# MotorControllerV2.net
KiCad netlist of a schematic drawn in EAGLE
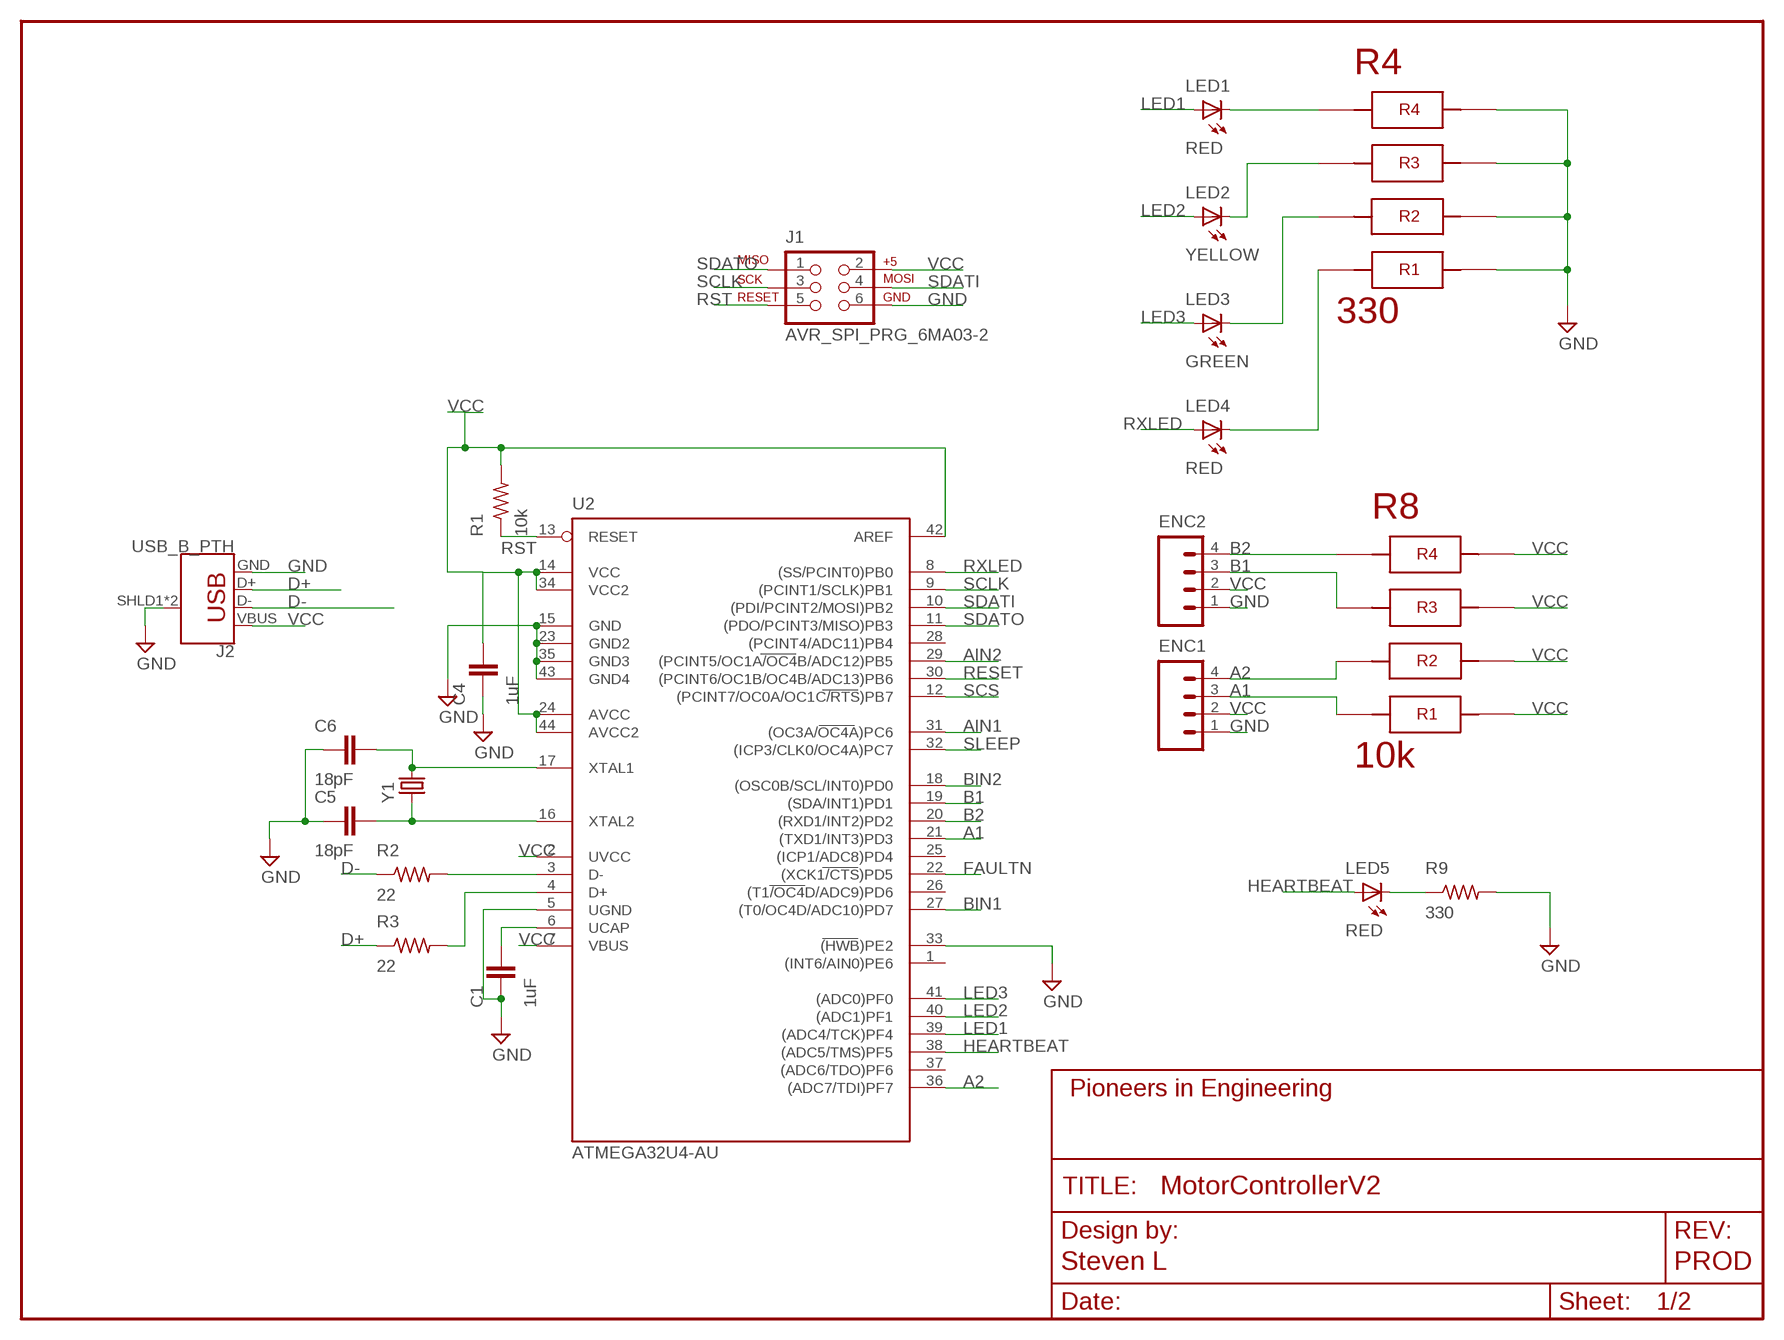
[diagram p0: schematic, sheet 1]
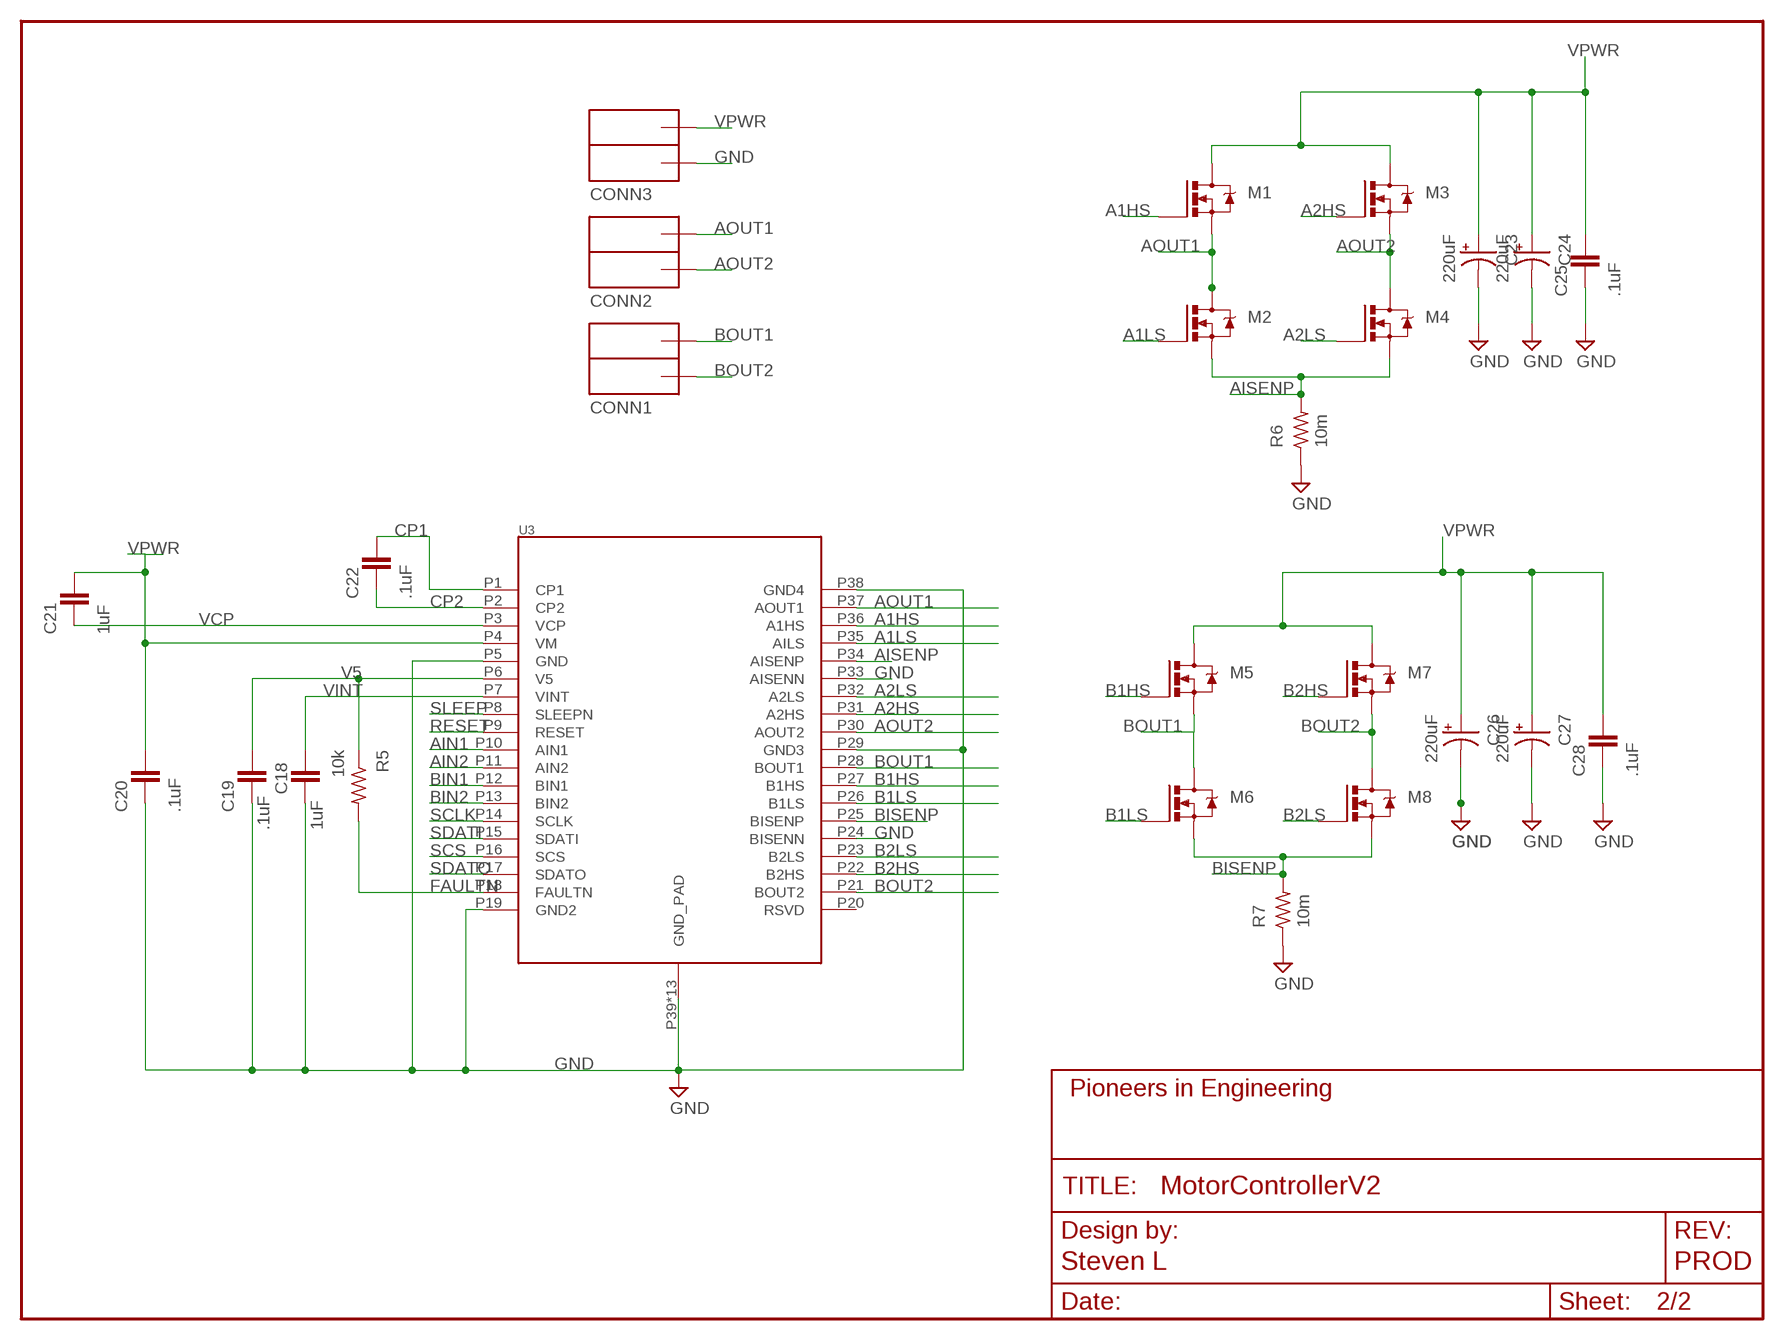
[diagram p1: schematic, sheet 2]

(export (version "E")
  (design (tool "Eeschema 10.0.6"))
  (components
    (comp (ref "C18")
      (value "1uF")
      (footprint "eagle-import:0603-CAP")
      (libsource (lib "eagle-import") (part "CAP0603-CAP"))
    )
    (comp (ref "C19")
      (value ".1uF")
      (footprint "eagle-import:0603-CAP")
      (libsource (lib "eagle-import") (part "CAP0603-CAP"))
    )
    (comp (ref "C20")
      (value ".1uF")
      (footprint "eagle-import:0603-CAP")
      (libsource (lib "eagle-import") (part "CAP0603-CAP"))
    )
    (comp (ref "C21")
      (value "1uF")
      (footprint "eagle-import:0603-CAP")
      (libsource (lib "eagle-import") (part "CAP0603-CAP"))
    )
    (comp (ref "C22")
      (value ".1uF")
      (footprint "eagle-import:0603-CAP")
      (libsource (lib "eagle-import") (part "CAP0603-CAP"))
    )
    (comp (ref "C23")
      (value "220uF")
      (footprint "eagle-import:NIPPON_F80")
      (libsource (lib "eagle-import") (part "CAP_POLF80"))
    )
    (comp (ref "C24")
      (value "220uF")
      (footprint "eagle-import:NIPPON_F80")
      (libsource (lib "eagle-import") (part "CAP_POLF80"))
    )
    (comp (ref "C25")
      (value ".1uF")
      (footprint "eagle-import:0603-CAP")
      (libsource (lib "eagle-import") (part "CAP0603-CAP"))
    )
    (comp (ref "C26")
      (value "220uF")
      (footprint "eagle-import:NIPPON_F80")
      (libsource (lib "eagle-import") (part "CAP_POLF80"))
    )
    (comp (ref "C27")
      (value "220uF")
      (footprint "eagle-import:NIPPON_F80")
      (libsource (lib "eagle-import") (part "CAP_POLF80"))
    )
    (comp (ref "C28")
      (value ".1uF")
      (footprint "eagle-import:0603-CAP")
      (libsource (lib "eagle-import") (part "CAP0603-CAP"))
    )
    (comp (ref "CONN1")
      (value "ANDERSONVERTICAL")
      (footprint "eagle-import:ANDERSON_VERTICAL")
      (libsource (lib "eagle-import") (part "ANDERSONVERTICAL"))
    )
    (comp (ref "CONN2")
      (value "ANDERSONVERTICAL")
      (footprint "eagle-import:ANDERSON_VERTICAL")
      (libsource (lib "eagle-import") (part "ANDERSONVERTICAL"))
    )
    (comp (ref "CONN3")
      (value "ANDERSONVERTICAL")
      (footprint "eagle-import:ANDERSON_VERTICAL")
      (libsource (lib "eagle-import") (part "ANDERSONVERTICAL"))
    )
    (comp (ref "M1")
      (value "NMOS_CSD17579Q3A")
      (footprint "eagle-import:DNH0008A")
      (fields (field (name "PART_NO") "CSD17579Q3A"))
      (libsource (lib "eagle-import") (part "NMOS_CSD17579Q3A"))
    )
    (comp (ref "M2")
      (value "NMOS_CSD17579Q3A")
      (footprint "eagle-import:DNH0008A")
      (fields (field (name "PART_NO") "CSD17579Q3A"))
      (libsource (lib "eagle-import") (part "NMOS_CSD17579Q3A"))
    )
    (comp (ref "M3")
      (value "NMOS_CSD17579Q3A")
      (footprint "eagle-import:DNH0008A")
      (fields (field (name "PART_NO") "CSD17579Q3A"))
      (libsource (lib "eagle-import") (part "NMOS_CSD17579Q3A"))
    )
    (comp (ref "M4")
      (value "NMOS_CSD17579Q3A")
      (footprint "eagle-import:DNH0008A")
      (fields (field (name "PART_NO") "CSD17579Q3A"))
      (libsource (lib "eagle-import") (part "NMOS_CSD17579Q3A"))
    )
    (comp (ref "M5")
      (value "NMOS_CSD17579Q3A")
      (footprint "eagle-import:DNH0008A")
      (fields (field (name "PART_NO") "CSD17579Q3A"))
      (libsource (lib "eagle-import") (part "NMOS_CSD17579Q3A"))
    )
    (comp (ref "M6")
      (value "NMOS_CSD17579Q3A")
      (footprint "eagle-import:DNH0008A")
      (fields (field (name "PART_NO") "CSD17579Q3A"))
      (libsource (lib "eagle-import") (part "NMOS_CSD17579Q3A"))
    )
    (comp (ref "M7")
      (value "NMOS_CSD17579Q3A")
      (footprint "eagle-import:DNH0008A")
      (fields (field (name "PART_NO") "CSD17579Q3A"))
      (libsource (lib "eagle-import") (part "NMOS_CSD17579Q3A"))
    )
    (comp (ref "M8")
      (value "NMOS_CSD17579Q3A")
      (footprint "eagle-import:DNH0008A")
      (fields (field (name "PART_NO") "CSD17579Q3A"))
      (libsource (lib "eagle-import") (part "NMOS_CSD17579Q3A"))
    )
    (comp (ref "R5")
      (value "10k")
      (footprint "eagle-import:R0603")
      (fields (field (name "MANUFACTURER") "Rohm Semiconductor"))
      (libsource (lib "eagle-import") (part "R-US_R0603"))
    )
    (comp (ref "R6")
      (value "10m")
      (footprint "eagle-import:R2512")
      (libsource (lib "eagle-import") (part "R-US_R2512"))
    )
    (comp (ref "R7")
      (value "10m")
      (footprint "eagle-import:R2512")
      (libsource (lib "eagle-import") (part "R-US_R2512"))
    )
    (comp (ref "U3")
      (value "DRV8704")
      (footprint "eagle-import:HTSSOP(38)")
      (libsource (lib "eagle-import") (part "DRV8704"))
    )
    (comp (ref "C1")
      (value "1uF")
      (footprint "eagle-import:0603-CAP")
      (libsource (lib "eagle-import") (part "CAP0603-CAP"))
    )
    (comp (ref "C4")
      (value "1uF")
      (footprint "eagle-import:0603-CAP")
      (libsource (lib "eagle-import") (part "CAP0603-CAP"))
    )
    (comp (ref "C5")
      (value "18pF")
      (footprint "eagle-import:0603-CAP")
      (libsource (lib "eagle-import") (part "CAP0603-CAP"))
    )
    (comp (ref "C6")
      (value "18pF")
      (footprint "eagle-import:0603-CAP")
      (libsource (lib "eagle-import") (part "CAP0603-CAP"))
    )
    (comp (ref "ENC1")
      (value "M041X04-MTA")
      (footprint "eagle-import:1X04-MTA")
      (libsource (lib "eagle-import") (part "M041X04-MTA"))
    )
    (comp (ref "ENC2")
      (value "M041X04-MTA")
      (footprint "eagle-import:1X04-MTA")
      (libsource (lib "eagle-import") (part "M041X04-MTA"))
    )
    (comp (ref "J1")
      (value "AVR_SPI_PRG_6MA03-2")
      (footprint "eagle-import:MA03-2")
      (libsource (lib "eagle-import") (part "AVR_SPI_PRG_6MA03-2"))
    )
    (comp (ref "J2")
      (value "USB_B_PTH")
      (footprint "eagle-import:USB-B-PTH")
      (libsource (lib "eagle-import") (part "USB_B_PTH"))
    )
    (comp (ref "LED1")
      (value "RED")
      (footprint "eagle-import:LED-1206")
      (libsource (lib "eagle-import") (part "LED1206"))
    )
    (comp (ref "LED2")
      (value "YELLOW")
      (footprint "eagle-import:LED-1206")
      (libsource (lib "eagle-import") (part "LED1206"))
    )
    (comp (ref "LED3")
      (value "GREEN")
      (footprint "eagle-import:LED-1206")
      (libsource (lib "eagle-import") (part "LED1206"))
    )
    (comp (ref "LED4")
      (value "RED")
      (footprint "eagle-import:LED-1206")
      (libsource (lib "eagle-import") (part "LED1206"))
    )
    (comp (ref "LED5")
      (value "RED")
      (footprint "eagle-import:LED-1206")
      (libsource (lib "eagle-import") (part "LED1206"))
    )
    (comp (ref "R1")
      (value "10k")
      (footprint "eagle-import:R0603")
      (fields (field (name "MANUFACTURER") "Rohm Semiconductor"))
      (libsource (lib "eagle-import") (part "R-US_R0603"))
    )
    (comp (ref "R2")
      (value "22")
      (footprint "eagle-import:R0603")
      (fields (field (name "MANUFACTURER") "Rohm Semiconductor"))
      (libsource (lib "eagle-import") (part "R-US_R0603"))
    )
    (comp (ref "R3")
      (value "22")
      (footprint "eagle-import:R0603")
      (fields (field (name "MANUFACTURER") "Rohm Semiconductor"))
      (libsource (lib "eagle-import") (part "R-US_R0603"))
    )
    (comp (ref "R4")
      (value "330")
      (footprint "eagle-import:4X-0603")
      (libsource (lib "eagle-import") (part "4X-0603"))
    )
    (comp (ref "R8")
      (value "10k")
      (footprint "eagle-import:4X-0603")
      (libsource (lib "eagle-import") (part "4X-0603"))
    )
    (comp (ref "R9")
      (value "330")
      (footprint "eagle-import:R0603")
      (fields (field (name "MANUFACTURER") "Rohm Semiconductor"))
      (libsource (lib "eagle-import") (part "R-US_R0603"))
    )
    (comp (ref "U2")
      (value "ATMEGA32U4-AU")
      (footprint "eagle-import:TQFP44")
      (libsource (lib "eagle-import") (part "ATMEGA32U4-AU"))
    )
    (comp (ref "Y1")
      (value "CRYSTAL10.5X4.8")
      (footprint "eagle-import:CRYSTAL-SMD-10.5X4.8-2PIN")
      (libsource (lib "eagle-import") (part "CRYSTAL10.5X4.8"))
    )
  )
  (nets
    (net (code "1") (name "A1") (class "Default")
      (node (ref "ENC1") (pin "3") (pinfunction "3_3") (pintype "passive"))
      (node (ref "R8") (pin "8") (pinfunction "8_8") (pintype "bidirectional"))
      (node (ref "U2") (pin "21") (pinfunction "(TXD1/INT3)PD3_21") (pintype "bidirectional"))
    )
    (net (code "2") (name "A1HS") (class "Default")
      (node (ref "M1") (pin "4") (pinfunction "G_4") (pintype "passive"))
      (node (ref "U3") (pin "P36") (pinfunction "A1HS_P36") (pintype "bidirectional"))
    )
    (net (code "3") (name "A1LS") (class "Default")
      (node (ref "M2") (pin "4") (pinfunction "G_4") (pintype "passive"))
      (node (ref "U3") (pin "P35") (pinfunction "AILS_P35") (pintype "bidirectional"))
    )
    (net (code "4") (name "A2") (class "Default")
      (node (ref "ENC1") (pin "4") (pinfunction "4_4") (pintype "passive"))
      (node (ref "R8") (pin "7") (pinfunction "7_7") (pintype "bidirectional"))
      (node (ref "U2") (pin "36") (pinfunction "(ADC7/TDI)PF7_36") (pintype "bidirectional"))
    )
    (net (code "5") (name "A2HS") (class "Default")
      (node (ref "M3") (pin "4") (pinfunction "G_4") (pintype "passive"))
      (node (ref "U3") (pin "P31") (pinfunction "A2HS_P31") (pintype "bidirectional"))
    )
    (net (code "6") (name "A2LS") (class "Default")
      (node (ref "M4") (pin "4") (pinfunction "G_4") (pintype "passive"))
      (node (ref "U3") (pin "P32") (pinfunction "A2LS_P32") (pintype "bidirectional"))
    )
    (net (code "7") (name "AIN1") (class "Default")
      (node (ref "U2") (pin "31") (pinfunction "(OC3A/OC4A)PC6_31") (pintype "bidirectional"))
      (node (ref "U3") (pin "P10") (pinfunction "AIN1_P10") (pintype "bidirectional"))
    )
    (net (code "8") (name "AIN2") (class "Default")
      (node (ref "U2") (pin "29") (pinfunction "(PCINT5/OC1A/OC4B/ADC12)PB5_29") (pintype "bidirectional"))
      (node (ref "U3") (pin "P11") (pinfunction "AIN2_P11") (pintype "bidirectional"))
    )
    (net (code "9") (name "AISENP") (class "Default")
      (node (ref "M2") (pin "1") (pinfunction "S_1") (pintype "passive"))
      (node (ref "M2") (pin "2") (pinfunction "S_2") (pintype "passive"))
      (node (ref "M2") (pin "3") (pinfunction "S_3") (pintype "passive"))
      (node (ref "M4") (pin "1") (pinfunction "S_1") (pintype "passive"))
      (node (ref "M4") (pin "2") (pinfunction "S_2") (pintype "passive"))
      (node (ref "M4") (pin "3") (pinfunction "S_3") (pintype "passive"))
      (node (ref "R6") (pin "2") (pinfunction "2_2") (pintype "passive"))
      (node (ref "U3") (pin "P34") (pinfunction "AISENP_P34") (pintype "bidirectional"))
    )
    (net (code "10") (name "AOUT1") (class "Default")
      (node (ref "CONN2") (pin "PIN1") (pinfunction "OUTB_PIN1") (pintype "bidirectional"))
      (node (ref "M1") (pin "1") (pinfunction "S_1") (pintype "passive"))
      (node (ref "M1") (pin "2") (pinfunction "S_2") (pintype "passive"))
      (node (ref "M1") (pin "3") (pinfunction "S_3") (pintype "passive"))
      (node (ref "M2") (pin "5") (pinfunction "D_5") (pintype "passive"))
      (node (ref "M2") (pin "6") (pinfunction "D_6") (pintype "passive"))
      (node (ref "M2") (pin "7") (pinfunction "D_7") (pintype "passive"))
      (node (ref "M2") (pin "8") (pinfunction "D_8") (pintype "passive"))
      (node (ref "M2") (pin "9") (pinfunction "D_9") (pintype "passive"))
      (node (ref "U3") (pin "P37") (pinfunction "AOUT1_P37") (pintype "bidirectional"))
    )
    (net (code "11") (name "AOUT2") (class "Default")
      (node (ref "CONN2") (pin "PIN2") (pinfunction "OUTA_PIN2") (pintype "bidirectional"))
      (node (ref "M3") (pin "1") (pinfunction "S_1") (pintype "passive"))
      (node (ref "M3") (pin "2") (pinfunction "S_2") (pintype "passive"))
      (node (ref "M3") (pin "3") (pinfunction "S_3") (pintype "passive"))
      (node (ref "M4") (pin "5") (pinfunction "D_5") (pintype "passive"))
      (node (ref "M4") (pin "6") (pinfunction "D_6") (pintype "passive"))
      (node (ref "M4") (pin "7") (pinfunction "D_7") (pintype "passive"))
      (node (ref "M4") (pin "8") (pinfunction "D_8") (pintype "passive"))
      (node (ref "M4") (pin "9") (pinfunction "D_9") (pintype "passive"))
      (node (ref "U3") (pin "P30") (pinfunction "AOUT2_P30") (pintype "bidirectional"))
    )
    (net (code "12") (name "B1") (class "Default")
      (node (ref "ENC2") (pin "3") (pinfunction "3_3") (pintype "passive"))
      (node (ref "R8") (pin "6") (pinfunction "6_6") (pintype "bidirectional"))
      (node (ref "U2") (pin "19") (pinfunction "(SDA/INT1)PD1_19") (pintype "bidirectional"))
    )
    (net (code "13") (name "B1HS") (class "Default")
      (node (ref "M5") (pin "4") (pinfunction "G_4") (pintype "passive"))
      (node (ref "U3") (pin "P27") (pinfunction "B1HS_P27") (pintype "bidirectional"))
    )
    (net (code "14") (name "B1LS") (class "Default")
      (node (ref "M6") (pin "4") (pinfunction "G_4") (pintype "passive"))
      (node (ref "U3") (pin "P26") (pinfunction "B1LS_P26") (pintype "bidirectional"))
    )
    (net (code "15") (name "B2") (class "Default")
      (node (ref "ENC2") (pin "4") (pinfunction "4_4") (pintype "passive"))
      (node (ref "R8") (pin "5") (pinfunction "5_5") (pintype "bidirectional"))
      (node (ref "U2") (pin "20") (pinfunction "(RXD1/INT2)PD2_20") (pintype "bidirectional"))
    )
    (net (code "16") (name "B2HS") (class "Default")
      (node (ref "M7") (pin "4") (pinfunction "G_4") (pintype "passive"))
      (node (ref "U3") (pin "P22") (pinfunction "B2HS_P22") (pintype "bidirectional"))
    )
    (net (code "17") (name "B2LS") (class "Default")
      (node (ref "M8") (pin "4") (pinfunction "G_4") (pintype "passive"))
      (node (ref "U3") (pin "P23") (pinfunction "B2LS_P23") (pintype "bidirectional"))
    )
    (net (code "18") (name "BIN1") (class "Default")
      (node (ref "U2") (pin "27") (pinfunction "(T0/OC4D/ADC10)PD7_27") (pintype "bidirectional"))
      (node (ref "U3") (pin "P12") (pinfunction "BIN1_P12") (pintype "bidirectional"))
    )
    (net (code "19") (name "BIN2") (class "Default")
      (node (ref "U2") (pin "18") (pinfunction "(OSC0B/SCL/INT0)PD0_18") (pintype "bidirectional"))
      (node (ref "U3") (pin "P13") (pinfunction "BIN2_P13") (pintype "bidirectional"))
    )
    (net (code "20") (name "BISENP") (class "Default")
      (node (ref "M6") (pin "1") (pinfunction "S_1") (pintype "passive"))
      (node (ref "M6") (pin "2") (pinfunction "S_2") (pintype "passive"))
      (node (ref "M6") (pin "3") (pinfunction "S_3") (pintype "passive"))
      (node (ref "M8") (pin "1") (pinfunction "S_1") (pintype "passive"))
      (node (ref "M8") (pin "2") (pinfunction "S_2") (pintype "passive"))
      (node (ref "M8") (pin "3") (pinfunction "S_3") (pintype "passive"))
      (node (ref "R7") (pin "2") (pinfunction "2_2") (pintype "passive"))
      (node (ref "U3") (pin "P25") (pinfunction "BISENP_P25") (pintype "bidirectional"))
    )
    (net (code "21") (name "BOUT1") (class "Default")
      (node (ref "CONN1") (pin "PIN1") (pinfunction "OUTB_PIN1") (pintype "bidirectional"))
      (node (ref "M5") (pin "1") (pinfunction "S_1") (pintype "passive"))
      (node (ref "M5") (pin "2") (pinfunction "S_2") (pintype "passive"))
      (node (ref "M5") (pin "3") (pinfunction "S_3") (pintype "passive"))
      (node (ref "M6") (pin "5") (pinfunction "D_5") (pintype "passive"))
      (node (ref "M6") (pin "6") (pinfunction "D_6") (pintype "passive"))
      (node (ref "M6") (pin "7") (pinfunction "D_7") (pintype "passive"))
      (node (ref "M6") (pin "8") (pinfunction "D_8") (pintype "passive"))
      (node (ref "M6") (pin "9") (pinfunction "D_9") (pintype "passive"))
      (node (ref "U3") (pin "P28") (pinfunction "BOUT1_P28") (pintype "bidirectional"))
    )
    (net (code "22") (name "BOUT2") (class "Default")
      (node (ref "CONN1") (pin "PIN2") (pinfunction "OUTA_PIN2") (pintype "bidirectional"))
      (node (ref "M7") (pin "1") (pinfunction "S_1") (pintype "passive"))
      (node (ref "M7") (pin "2") (pinfunction "S_2") (pintype "passive"))
      (node (ref "M7") (pin "3") (pinfunction "S_3") (pintype "passive"))
      (node (ref "M8") (pin "5") (pinfunction "D_5") (pintype "passive"))
      (node (ref "M8") (pin "6") (pinfunction "D_6") (pintype "passive"))
      (node (ref "M8") (pin "7") (pinfunction "D_7") (pintype "passive"))
      (node (ref "M8") (pin "8") (pinfunction "D_8") (pintype "passive"))
      (node (ref "M8") (pin "9") (pinfunction "D_9") (pintype "passive"))
      (node (ref "U3") (pin "P21") (pinfunction "BOUT2_P21") (pintype "bidirectional"))
    )
    (net (code "23") (name "CP1") (class "Default")
      (node (ref "C22") (pin "2") (pinfunction "2_2") (pintype "passive"))
      (node (ref "U3") (pin "P1") (pinfunction "CP1_P1") (pintype "bidirectional"))
    )
    (net (code "24") (name "CP2") (class "Default")
      (node (ref "C22") (pin "1") (pinfunction "1_1") (pintype "passive"))
      (node (ref "U3") (pin "P2") (pinfunction "CP2_P2") (pintype "bidirectional"))
    )
    (net (code "25") (name "D+") (class "Default")
      (node (ref "J2") (pin "D+") (pinfunction "D+_D+") (pintype "bidirectional"))
      (node (ref "R3") (pin "1") (pinfunction "1_1") (pintype "passive"))
    )
    (net (code "26") (name "D-") (class "Default")
      (node (ref "J2") (pin "D-") (pinfunction "D-_D-") (pintype "bidirectional"))
      (node (ref "R2") (pin "1") (pinfunction "1_1") (pintype "passive"))
    )
    (net (code "27") (name "FAULTN") (class "Default")
      (node (ref "R5") (pin "2") (pinfunction "2_2") (pintype "passive"))
      (node (ref "U2") (pin "22") (pinfunction "(XCK1/CTS)PD5_22") (pintype "bidirectional"))
      (node (ref "U3") (pin "P18") (pinfunction "FAULTN_P18") (pintype "bidirectional"))
    )
    (net (code "28") (name "GND") (class "Default")
      (node (ref "C1") (pin "1") (pinfunction "1_1") (pintype "passive"))
      (node (ref "C18") (pin "1") (pinfunction "1_1") (pintype "passive"))
      (node (ref "C19") (pin "1") (pinfunction "1_1") (pintype "passive"))
      (node (ref "C20") (pin "1") (pinfunction "1_1") (pintype "passive"))
      (node (ref "C23") (pin "-") (pinfunction "-_-") (pintype "passive"))
      (node (ref "C24") (pin "-") (pinfunction "-_-") (pintype "passive"))
      (node (ref "C25") (pin "1") (pinfunction "1_1") (pintype "passive"))
      (node (ref "C26") (pin "-") (pinfunction "-_-") (pintype "passive"))
      (node (ref "C27") (pin "-") (pinfunction "-_-") (pintype "passive"))
      (node (ref "C28") (pin "1") (pinfunction "1_1") (pintype "passive"))
      (node (ref "C4") (pin "1") (pinfunction "1_1") (pintype "passive"))
      (node (ref "C5") (pin "1") (pinfunction "1_1") (pintype "passive"))
      (node (ref "C6") (pin "1") (pinfunction "1_1") (pintype "passive"))
      (node (ref "CONN3") (pin "PIN2") (pinfunction "OUTA_PIN2") (pintype "bidirectional"))
      (node (ref "ENC1") (pin "1") (pinfunction "1_1") (pintype "passive"))
      (node (ref "ENC2") (pin "1") (pinfunction "1_1") (pintype "passive"))
      (node (ref "J1") (pin "6") (pinfunction "6_6") (pintype "passive"))
      (node (ref "J2") (pin "GND") (pinfunction "GND_GND") (pintype "power_in"))
      (node (ref "J2") (pin "SHLD1") (pinfunction "SHIELD_SHLD1") (pintype "bidirectional"))
      (node (ref "J2") (pin "SHLD2") (pinfunction "SHIELD_SHLD2") (pintype "bidirectional"))
      (node (ref "R4") (pin "1") (pinfunction "1_1") (pintype "bidirectional"))
      (node (ref "R4") (pin "2") (pinfunction "2_2") (pintype "bidirectional"))
      (node (ref "R4") (pin "3") (pinfunction "3_3") (pintype "bidirectional"))
      (node (ref "R4") (pin "4") (pinfunction "4_4") (pintype "bidirectional"))
      (node (ref "R6") (pin "1") (pinfunction "1_1") (pintype "passive"))
      (node (ref "R7") (pin "1") (pinfunction "1_1") (pintype "passive"))
      (node (ref "R9") (pin "2") (pinfunction "2_2") (pintype "passive"))
      (node (ref "U2") (pin "15") (pinfunction "GND_15") (pintype "bidirectional"))
      (node (ref "U2") (pin "23") (pinfunction "GND2_23") (pintype "bidirectional"))
      (node (ref "U2") (pin "33") (pinfunction "(HWB)PE2_33") (pintype "bidirectional"))
      (node (ref "U2") (pin "35") (pinfunction "GND3_35") (pintype "bidirectional"))
      (node (ref "U2") (pin "43") (pinfunction "GND4_43") (pintype "bidirectional"))
      (node (ref "U2") (pin "5") (pinfunction "UGND_5") (pintype "bidirectional"))
      (node (ref "U3") (pin "P19") (pinfunction "GND2_P19") (pintype "bidirectional"))
      (node (ref "U3") (pin "P24") (pinfunction "BISENN_P24") (pintype "bidirectional"))
      (node (ref "U3") (pin "P29") (pinfunction "GND3_P29") (pintype "bidirectional"))
      (node (ref "U3") (pin "P33") (pinfunction "AISENN_P33") (pintype "bidirectional"))
      (node (ref "U3") (pin "P38") (pinfunction "GND4_P38") (pintype "bidirectional"))
      (node (ref "U3") (pin "P39") (pinfunction "GND_PAD_P39") (pintype "bidirectional"))
      (node (ref "U3") (pin "P40") (pinfunction "GND_PAD_P40") (pintype "bidirectional"))
      (node (ref "U3") (pin "P41") (pinfunction "GND_PAD_P41") (pintype "bidirectional"))
      (node (ref "U3") (pin "P42") (pinfunction "GND_PAD_P42") (pintype "bidirectional"))
      (node (ref "U3") (pin "P43") (pinfunction "GND_PAD_P43") (pintype "bidirectional"))
      (node (ref "U3") (pin "P44") (pinfunction "GND_PAD_P44") (pintype "bidirectional"))
      (node (ref "U3") (pin "P45") (pinfunction "GND_PAD_P45") (pintype "bidirectional"))
      (node (ref "U3") (pin "P46") (pinfunction "GND_PAD_P46") (pintype "bidirectional"))
      (node (ref "U3") (pin "P47") (pinfunction "GND_PAD_P47") (pintype "bidirectional"))
      (node (ref "U3") (pin "P48") (pinfunction "GND_PAD_P48") (pintype "bidirectional"))
      (node (ref "U3") (pin "P49") (pinfunction "GND_PAD_P49") (pintype "bidirectional"))
      (node (ref "U3") (pin "P5") (pinfunction "GND_P5") (pintype "bidirectional"))
      (node (ref "U3") (pin "P50") (pinfunction "GND_PAD_P50") (pintype "bidirectional"))
      (node (ref "U3") (pin "P51") (pinfunction "GND_PAD_P51") (pintype "bidirectional"))
    )
    (net (code "29") (name "HEARTBEAT") (class "Default")
      (node (ref "LED5") (pin "A") (pinfunction "A_A") (pintype "passive"))
      (node (ref "U2") (pin "38") (pinfunction "(ADC5/TMS)PF5_38") (pintype "bidirectional"))
    )
    (net (code "30") (name "LED1") (class "Default")
      (node (ref "LED1") (pin "A") (pinfunction "A_A") (pintype "passive"))
      (node (ref "U2") (pin "39") (pinfunction "(ADC4/TCK)PF4_39") (pintype "bidirectional"))
    )
    (net (code "31") (name "LED2") (class "Default")
      (node (ref "LED2") (pin "A") (pinfunction "A_A") (pintype "passive"))
      (node (ref "U2") (pin "40") (pinfunction "(ADC1)PF1_40") (pintype "bidirectional"))
    )
    (net (code "32") (name "LED3") (class "Default")
      (node (ref "LED3") (pin "A") (pinfunction "A_A") (pintype "passive"))
      (node (ref "U2") (pin "41") (pinfunction "(ADC0)PF0_41") (pintype "bidirectional"))
    )
    (net (code "33") (name "Net-(LED1-PadC)") (class "Default")
      (node (ref "LED1") (pin "C") (pinfunction "C_C") (pintype "passive"))
      (node (ref "R4") (pin "5") (pinfunction "5_5") (pintype "bidirectional"))
    )
    (net (code "34") (name "Net-(LED2-PadC)") (class "Default")
      (node (ref "LED2") (pin "C") (pinfunction "C_C") (pintype "passive"))
      (node (ref "R4") (pin "6") (pinfunction "6_6") (pintype "bidirectional"))
    )
    (net (code "35") (name "Net-(LED3-PadC)") (class "Default")
      (node (ref "LED3") (pin "C") (pinfunction "C_C") (pintype "passive"))
      (node (ref "R4") (pin "7") (pinfunction "7_7") (pintype "bidirectional"))
    )
    (net (code "36") (name "Net-(LED4-PadC)") (class "Default")
      (node (ref "LED4") (pin "C") (pinfunction "C_C") (pintype "passive"))
      (node (ref "R4") (pin "8") (pinfunction "8_8") (pintype "bidirectional"))
    )
    (net (code "37") (name "Net-(LED5-PadC)") (class "Default")
      (node (ref "LED5") (pin "C") (pinfunction "C_C") (pintype "passive"))
      (node (ref "R9") (pin "1") (pinfunction "1_1") (pintype "passive"))
    )
    (net (code "38") (name "Net-(U2-D+)") (class "Default")
      (node (ref "R3") (pin "2") (pinfunction "2_2") (pintype "passive"))
      (node (ref "U2") (pin "4") (pinfunction "D+_4") (pintype "bidirectional"))
    )
    (net (code "39") (name "Net-(U2-D-)") (class "Default")
      (node (ref "R2") (pin "2") (pinfunction "2_2") (pintype "passive"))
      (node (ref "U2") (pin "3") (pinfunction "D-_3") (pintype "bidirectional"))
    )
    (net (code "40") (name "Net-(U2-UCAP)") (class "Default")
      (node (ref "C1") (pin "2") (pinfunction "2_2") (pintype "passive"))
      (node (ref "U2") (pin "6") (pinfunction "UCAP_6") (pintype "bidirectional"))
    )
    (net (code "41") (name "Net-(U2-XTAL1)") (class "Default")
      (node (ref "C6") (pin "2") (pinfunction "2_2") (pintype "passive"))
      (node (ref "U2") (pin "17") (pinfunction "XTAL1_17") (pintype "bidirectional"))
      (node (ref "Y1") (pin "P$2") (pinfunction "2_P$2") (pintype "passive"))
    )
    (net (code "42") (name "Net-(U2-XTAL2)") (class "Default")
      (node (ref "C5") (pin "2") (pinfunction "2_2") (pintype "passive"))
      (node (ref "U2") (pin "16") (pinfunction "XTAL2_16") (pintype "bidirectional"))
      (node (ref "Y1") (pin "P$1") (pinfunction "1_P$1") (pintype "passive"))
    )
    (net (code "43") (name "RESET") (class "Default")
      (node (ref "U2") (pin "30") (pinfunction "(PCINT6/OC1B/OC4B/ADC13)PB6_30") (pintype "bidirectional"))
      (node (ref "U3") (pin "P9") (pinfunction "RESET_P9") (pintype "bidirectional"))
    )
    (net (code "44") (name "RST") (class "Default")
      (node (ref "J1") (pin "5") (pinfunction "5_5") (pintype "passive"))
      (node (ref "R1") (pin "1") (pinfunction "1_1") (pintype "passive"))
      (node (ref "U2") (pin "13") (pinfunction "RESET_13") (pintype "bidirectional"))
    )
    (net (code "45") (name "RXLED") (class "Default")
      (node (ref "LED4") (pin "A") (pinfunction "A_A") (pintype "passive"))
      (node (ref "U2") (pin "8") (pinfunction "(SS/PCINT0)PB0_8") (pintype "bidirectional"))
    )
    (net (code "46") (name "SCLK") (class "Default")
      (node (ref "J1") (pin "3") (pinfunction "3_3") (pintype "passive"))
      (node (ref "U2") (pin "9") (pinfunction "(PCINT1/SCLK)PB1_9") (pintype "bidirectional"))
      (node (ref "U3") (pin "P14") (pinfunction "SCLK_P14") (pintype "bidirectional"))
    )
    (net (code "47") (name "SCS") (class "Default")
      (node (ref "U2") (pin "12") (pinfunction "(PCINT7/OC0A/OC1C/RTS)PB7_12") (pintype "bidirectional"))
      (node (ref "U3") (pin "P16") (pinfunction "SCS_P16") (pintype "bidirectional"))
    )
    (net (code "48") (name "SDATI") (class "Default")
      (node (ref "J1") (pin "4") (pinfunction "4_4") (pintype "passive"))
      (node (ref "U2") (pin "10") (pinfunction "(PDI/PCINT2/MOSI)PB2_10") (pintype "bidirectional"))
      (node (ref "U3") (pin "P15") (pinfunction "SDATI_P15") (pintype "bidirectional"))
    )
    (net (code "49") (name "SDATO") (class "Default")
      (node (ref "J1") (pin "1") (pinfunction "1_1") (pintype "passive"))
      (node (ref "U2") (pin "11") (pinfunction "(PDO/PCINT3/MISO)PB3_11") (pintype "bidirectional"))
      (node (ref "U3") (pin "P17") (pinfunction "SDATO_P17") (pintype "bidirectional"))
    )
    (net (code "50") (name "SLEEP") (class "Default")
      (node (ref "U2") (pin "32") (pinfunction "(ICP3/CLK0/OC4A)PC7_32") (pintype "bidirectional"))
      (node (ref "U3") (pin "P8") (pinfunction "SLEEPN_P8") (pintype "bidirectional"))
    )
    (net (code "51") (name "V5") (class "Default")
      (node (ref "C19") (pin "2") (pinfunction "2_2") (pintype "passive"))
      (node (ref "R5") (pin "1") (pinfunction "1_1") (pintype "passive"))
      (node (ref "U3") (pin "P6") (pinfunction "V5_P6") (pintype "bidirectional"))
    )
    (net (code "52") (name "VCC") (class "Default")
      (node (ref "C4") (pin "2") (pinfunction "2_2") (pintype "passive"))
      (node (ref "ENC1") (pin "2") (pinfunction "2_2") (pintype "passive"))
      (node (ref "ENC2") (pin "2") (pinfunction "2_2") (pintype "passive"))
      (node (ref "J1") (pin "2") (pinfunction "2_2") (pintype "passive"))
      (node (ref "J2") (pin "VBUS") (pinfunction "VBUS_VBUS") (pintype "power_in"))
      (node (ref "R1") (pin "2") (pinfunction "2_2") (pintype "passive"))
      (node (ref "R8") (pin "1") (pinfunction "1_1") (pintype "bidirectional"))
      (node (ref "R8") (pin "2") (pinfunction "2_2") (pintype "bidirectional"))
      (node (ref "R8") (pin "3") (pinfunction "3_3") (pintype "bidirectional"))
      (node (ref "R8") (pin "4") (pinfunction "4_4") (pintype "bidirectional"))
      (node (ref "U2") (pin "14") (pinfunction "VCC_14") (pintype "bidirectional"))
      (node (ref "U2") (pin "2") (pinfunction "UVCC_2") (pintype "bidirectional"))
      (node (ref "U2") (pin "24") (pinfunction "AVCC_24") (pintype "bidirectional"))
      (node (ref "U2") (pin "34") (pinfunction "VCC2_34") (pintype "bidirectional"))
      (node (ref "U2") (pin "42") (pinfunction "AREF_42") (pintype "bidirectional"))
      (node (ref "U2") (pin "44") (pinfunction "AVCC2_44") (pintype "bidirectional"))
      (node (ref "U2") (pin "7") (pinfunction "VBUS_7") (pintype "bidirectional"))
    )
    (net (code "53") (name "VCP") (class "Default")
      (node (ref "C21") (pin "1") (pinfunction "1_1") (pintype "passive"))
      (node (ref "U3") (pin "P3") (pinfunction "VCP_P3") (pintype "bidirectional"))
    )
    (net (code "54") (name "VINT") (class "Default")
      (node (ref "C18") (pin "2") (pinfunction "2_2") (pintype "passive"))
      (node (ref "U3") (pin "P7") (pinfunction "VINT_P7") (pintype "bidirectional"))
    )
    (net (code "55") (name "VPWR") (class "Default")
      (node (ref "C20") (pin "2") (pinfunction "2_2") (pintype "passive"))
      (node (ref "C21") (pin "2") (pinfunction "2_2") (pintype "passive"))
      (node (ref "C23") (pin "+") (pinfunction "+_+") (pintype "passive"))
      (node (ref "C24") (pin "+") (pinfunction "+_+") (pintype "passive"))
      (node (ref "C25") (pin "2") (pinfunction "2_2") (pintype "passive"))
      (node (ref "C26") (pin "+") (pinfunction "+_+") (pintype "passive"))
      (node (ref "C27") (pin "+") (pinfunction "+_+") (pintype "passive"))
      (node (ref "C28") (pin "2") (pinfunction "2_2") (pintype "passive"))
      (node (ref "CONN3") (pin "PIN1") (pinfunction "OUTB_PIN1") (pintype "bidirectional"))
      (node (ref "M1") (pin "5") (pinfunction "D_5") (pintype "passive"))
      (node (ref "M1") (pin "6") (pinfunction "D_6") (pintype "passive"))
      (node (ref "M1") (pin "7") (pinfunction "D_7") (pintype "passive"))
      (node (ref "M1") (pin "8") (pinfunction "D_8") (pintype "passive"))
      (node (ref "M1") (pin "9") (pinfunction "D_9") (pintype "passive"))
      (node (ref "M3") (pin "5") (pinfunction "D_5") (pintype "passive"))
      (node (ref "M3") (pin "6") (pinfunction "D_6") (pintype "passive"))
      (node (ref "M3") (pin "7") (pinfunction "D_7") (pintype "passive"))
      (node (ref "M3") (pin "8") (pinfunction "D_8") (pintype "passive"))
      (node (ref "M3") (pin "9") (pinfunction "D_9") (pintype "passive"))
      (node (ref "M5") (pin "5") (pinfunction "D_5") (pintype "passive"))
      (node (ref "M5") (pin "6") (pinfunction "D_6") (pintype "passive"))
      (node (ref "M5") (pin "7") (pinfunction "D_7") (pintype "passive"))
      (node (ref "M5") (pin "8") (pinfunction "D_8") (pintype "passive"))
      (node (ref "M5") (pin "9") (pinfunction "D_9") (pintype "passive"))
      (node (ref "M7") (pin "5") (pinfunction "D_5") (pintype "passive"))
      (node (ref "M7") (pin "6") (pinfunction "D_6") (pintype "passive"))
      (node (ref "M7") (pin "7") (pinfunction "D_7") (pintype "passive"))
      (node (ref "M7") (pin "8") (pinfunction "D_8") (pintype "passive"))
      (node (ref "M7") (pin "9") (pinfunction "D_9") (pintype "passive"))
      (node (ref "U3") (pin "P4") (pinfunction "VM_P4") (pintype "bidirectional"))
    )
    (net (code "56") (name "unconnected-(U2-(ADC6{slash}TDO)PF6-Pad37)") (class "Default")
      (node (ref "U2") (pin "37") (pinfunction "(ADC6/TDO)PF6_37") (pintype "bidirectional"))
    )
    (net (code "57") (name "unconnected-(U2-(ICP1{slash}ADC8)PD4-Pad25)") (class "Default")
      (node (ref "U2") (pin "25") (pinfunction "(ICP1/ADC8)PD4_25") (pintype "bidirectional"))
    )
    (net (code "58") (name "unconnected-(U2-(INT6{slash}AIN0)PE6-Pad1)") (class "Default")
      (node (ref "U2") (pin "1") (pinfunction "(INT6/AIN0)PE6_1") (pintype "bidirectional"))
    )
    (net (code "59") (name "unconnected-(U2-(PCINT4{slash}ADC11)PB4-Pad28)") (class "Default")
      (node (ref "U2") (pin "28") (pinfunction "(PCINT4/ADC11)PB4_28") (pintype "bidirectional"))
    )
    (net (code "60") (name "unconnected-(U2-(T1{slash}OC4D{slash}ADC9)PD6-Pad26)") (class "Default")
      (node (ref "U2") (pin "26") (pinfunction "(T1/OC4D/ADC9)PD6_26") (pintype "bidirectional"))
    )
    (net (code "61") (name "unconnected-(U3-RSVD-PadP20)") (class "Default")
      (node (ref "U3") (pin "P20") (pinfunction "RSVD_P20") (pintype "bidirectional"))
    )
  )
)
